# IMTM-SCH01.net
KiCad netlist of a schematic drawn in Altium Designer
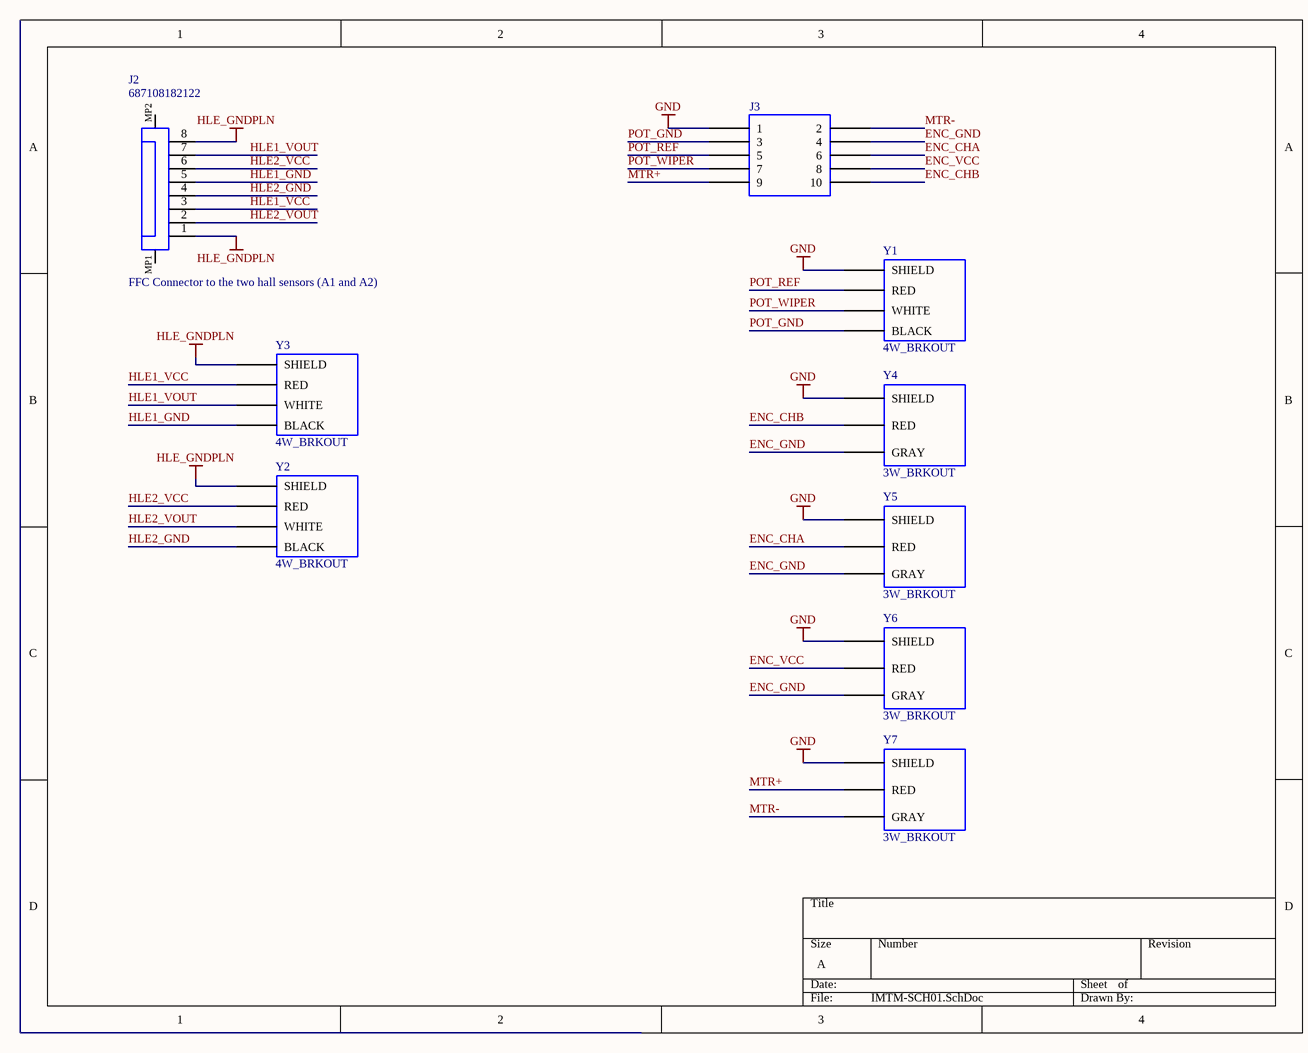
[diagram p0: IMTM-SCH01.SchDoc]

(export (version "E")
  (design (tool "Eeschema 10.0.6"))
  (components
    (comp (ref "J2")
      (value "687108182122")
      (footprint "PCBComponent_1")
      (description "CONN FFC FPC 8POS 0.5MM R/A")
      (fields (field (name "MANUFACTURER") "Wurth Electronics"))
      (libsource (lib "SchLibrary") (part "687108182122"))
    )
    (comp (ref "J3")
      (value "B10B-PHDSS(LF)(SN)(P)")
      (footprint "B10B-PHDSS(LF)(SN)(P)")
      (description "JST (JAPAN SOLDERLESS TERMINALS) - B10B-PHDSS(LF)(SN)(P) - CONNECTOR, HEADER, 10POS, 2MM, 2ROW")
      (fields (field (name "MANUFACTURER") "JST"))
      (libsource (lib "SchLibrary") (part "B10B-PHDSS(LF)(SN)(P)"))
    )
    (comp (ref "Y1")
      (value "4W_BRKOUT")
      (footprint "4W_BRKOUT")
      (libsource (lib "SchLibrary") (part "4W_BRKOUT"))
    )
    (comp (ref "Y2")
      (value "4W_BRKOUT")
      (footprint "4W_BRKOUT")
      (libsource (lib "SchLibrary") (part "4W_BRKOUT"))
    )
    (comp (ref "Y3")
      (value "4W_BRKOUT")
      (footprint "4W_BRKOUT")
      (libsource (lib "SchLibrary") (part "4W_BRKOUT"))
    )
    (comp (ref "Y4")
      (value "3W_BRKOUT")
      (footprint "3W_BRKOUT")
      (libsource (lib "SchLibrary") (part "3W_BRKOUT"))
    )
    (comp (ref "Y5")
      (value "3W_BRKOUT")
      (footprint "3W_BRKOUT")
      (libsource (lib "SchLibrary") (part "3W_BRKOUT"))
    )
    (comp (ref "Y6")
      (value "3W_BRKOUT")
      (footprint "3W_BRKOUT")
      (libsource (lib "SchLibrary") (part "3W_BRKOUT"))
    )
    (comp (ref "Y7")
      (value "3W_BRKOUT")
      (footprint "3W_BRKOUT")
      (libsource (lib "SchLibrary") (part "3W_BRKOUT"))
    )
  )
  (nets
    (net (code "1") (name "/ENC_CHA") (class "Default")
      (node (ref "J3") (pin "6") (pinfunction "6_6") (pintype "passive"))
      (node (ref "Y5") (pin "2") (pinfunction "RED_2") (pintype "passive"))
    )
    (net (code "2") (name "/ENC_CHB") (class "Default")
      (node (ref "J3") (pin "10") (pinfunction "10_10") (pintype "passive"))
      (node (ref "Y4") (pin "2") (pinfunction "RED_2") (pintype "passive"))
    )
    (net (code "3") (name "/ENC_GND") (class "Default")
      (node (ref "J3") (pin "4") (pinfunction "4_4") (pintype "passive"))
      (node (ref "Y4") (pin "3") (pinfunction "GRAY_3") (pintype "passive"))
      (node (ref "Y5") (pin "3") (pinfunction "GRAY_3") (pintype "passive"))
      (node (ref "Y6") (pin "3") (pinfunction "GRAY_3") (pintype "passive"))
    )
    (net (code "4") (name "/ENC_VCC") (class "Default")
      (node (ref "J3") (pin "8") (pinfunction "8_8") (pintype "passive"))
      (node (ref "Y6") (pin "2") (pinfunction "RED_2") (pintype "passive"))
    )
    (net (code "5") (name "/HLE1_GND") (class "Default")
      (node (ref "J2") (pin "5") (pinfunction "5_5") (pintype "passive"))
      (node (ref "Y3") (pin "4") (pinfunction "BLACK_4") (pintype "passive"))
    )
    (net (code "6") (name "/HLE1_VCC") (class "Default")
      (node (ref "J2") (pin "3") (pinfunction "3_3") (pintype "passive"))
      (node (ref "Y3") (pin "2") (pinfunction "RED_2") (pintype "passive"))
    )
    (net (code "7") (name "/HLE1_VOUT") (class "Default")
      (node (ref "J2") (pin "7") (pinfunction "7_7") (pintype "passive"))
      (node (ref "Y3") (pin "3") (pinfunction "WHITE_3") (pintype "passive"))
    )
    (net (code "8") (name "/HLE2_GND") (class "Default")
      (node (ref "J2") (pin "4") (pinfunction "4_4") (pintype "passive"))
      (node (ref "Y2") (pin "4") (pinfunction "BLACK_4") (pintype "passive"))
    )
    (net (code "9") (name "/HLE2_VCC") (class "Default")
      (node (ref "J2") (pin "6") (pinfunction "6_6") (pintype "passive"))
      (node (ref "Y2") (pin "2") (pinfunction "RED_2") (pintype "passive"))
    )
    (net (code "10") (name "/HLE2_VOUT") (class "Default")
      (node (ref "J2") (pin "2") (pinfunction "2_2") (pintype "passive"))
      (node (ref "Y2") (pin "3") (pinfunction "WHITE_3") (pintype "passive"))
    )
    (net (code "11") (name "/MTR+") (class "Default")
      (node (ref "J3") (pin "9") (pinfunction "9_9") (pintype "passive"))
      (node (ref "Y7") (pin "2") (pinfunction "RED_2") (pintype "passive"))
    )
    (net (code "12") (name "/MTR-") (class "Default")
      (node (ref "J3") (pin "2") (pinfunction "2_2") (pintype "passive"))
      (node (ref "Y7") (pin "3") (pinfunction "GRAY_3") (pintype "passive"))
    )
    (net (code "13") (name "/POT_GND") (class "Default")
      (node (ref "J3") (pin "3") (pinfunction "3_3") (pintype "passive"))
      (node (ref "Y1") (pin "4") (pinfunction "BLACK_4") (pintype "passive"))
    )
    (net (code "14") (name "/POT_REF") (class "Default")
      (node (ref "J3") (pin "5") (pinfunction "5_5") (pintype "passive"))
      (node (ref "Y1") (pin "2") (pinfunction "RED_2") (pintype "passive"))
    )
    (net (code "15") (name "/POT_WIPER") (class "Default")
      (node (ref "J3") (pin "7") (pinfunction "7_7") (pintype "passive"))
      (node (ref "Y1") (pin "3") (pinfunction "WHITE_3") (pintype "passive"))
    )
    (net (code "16") (name "GND") (class "Default")
      (node (ref "J3") (pin "1") (pinfunction "1_1") (pintype "passive"))
      (node (ref "Y1") (pin "1") (pinfunction "SHIELD_1") (pintype "passive"))
      (node (ref "Y4") (pin "1") (pinfunction "SHIELD_1") (pintype "passive"))
      (node (ref "Y5") (pin "1") (pinfunction "SHIELD_1") (pintype "passive"))
      (node (ref "Y6") (pin "1") (pinfunction "SHIELD_1") (pintype "passive"))
      (node (ref "Y7") (pin "1") (pinfunction "SHIELD_1") (pintype "passive"))
    )
    (net (code "17") (name "HLE_GNDPLN") (class "Default")
      (node (ref "J2") (pin "1") (pinfunction "1_1") (pintype "passive"))
      (node (ref "J2") (pin "8") (pinfunction "8_8") (pintype "passive"))
      (node (ref "Y2") (pin "1") (pinfunction "SHIELD_1") (pintype "passive"))
      (node (ref "Y3") (pin "1") (pinfunction "SHIELD_1") (pintype "passive"))
    )
    (net (code "18") (name "unconnected-(J2-PadMP1)") (class "Default")
      (node (ref "J2") (pin "MP1") (pinfunction "MP1_MP1") (pintype "passive"))
    )
    (net (code "19") (name "unconnected-(J2-PadMP2)") (class "Default")
      (node (ref "J2") (pin "MP2") (pinfunction "MP2_MP2") (pintype "passive"))
    )
  )
)
